# LIS3MDL.net
KiCad netlist of a schematic drawn in EAGLE
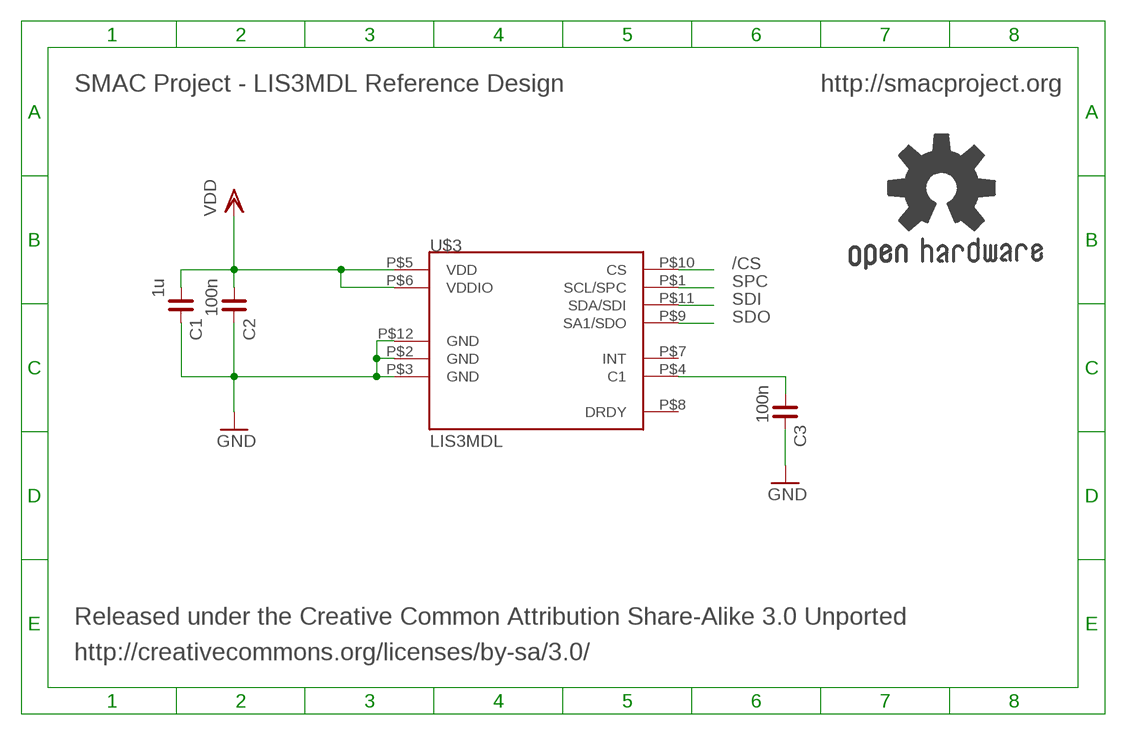
[diagram p0: schematic, sheet 1]

(export (version "E")
  (design (tool "Eeschema 10.0.6"))
  (components
    (comp (ref "C1")
      (value "1u")
      (footprint "eagle-import:C0402")
      (libsource (lib "eagle-import") (part "C_0402"))
    )
    (comp (ref "C2")
      (value "100n")
      (footprint "eagle-import:C0402")
      (libsource (lib "eagle-import") (part "C_0402"))
    )
    (comp (ref "C3")
      (value "100n")
      (footprint "eagle-import:C0402")
      (libsource (lib "eagle-import") (part "C_0402"))
    )
    (comp (ref "GOLD_ORB_SM1")
      (value "OSHWLOGO_REF_SM")
      (footprint "eagle-import:OSHW2REF")
      (libsource (lib "eagle-import") (part "OSHWLOGO_REF_SM"))
    )
    (comp (ref "U$3")
      (value "LIS3MDL")
      (footprint "eagle-import:VFLGA-2X2X1")
      (libsource (lib "eagle-import") (part "LIS3MDL"))
    )
  )
  (nets
    (net (code "1") (name "/SDI") (class "Default")
      (node (ref "U$3") (pin "P$11") (pinfunction "SDA/SDI_P$11") (pintype "bidirectional"))
    )
    (net (code "2") (name "/SDO") (class "Default")
      (node (ref "U$3") (pin "P$9") (pinfunction "SA1/SDO_P$9") (pintype "bidirectional"))
    )
    (net (code "3") (name "/SPC") (class "Default")
      (node (ref "U$3") (pin "P$1") (pinfunction "SCL/SPC_P$1") (pintype "bidirectional"))
    )
    (net (code "4") (name "/{slash}CS") (class "Default")
      (node (ref "U$3") (pin "P$10") (pinfunction "CS_P$10") (pintype "bidirectional"))
    )
    (net (code "5") (name "GND") (class "Default")
      (node (ref "C1") (pin "2") (pinfunction "2_2") (pintype "passive"))
      (node (ref "C2") (pin "2") (pinfunction "2_2") (pintype "passive"))
      (node (ref "C3") (pin "2") (pinfunction "2_2") (pintype "passive"))
      (node (ref "U$3") (pin "P$12") (pinfunction "GND_P$12") (pintype "bidirectional"))
      (node (ref "U$3") (pin "P$2") (pinfunction "GND_P$2") (pintype "bidirectional"))
      (node (ref "U$3") (pin "P$3") (pinfunction "GND_P$3") (pintype "bidirectional"))
    )
    (net (code "6") (name "Net-(U$3-C1)") (class "Default")
      (node (ref "C3") (pin "1") (pinfunction "1_1") (pintype "passive"))
      (node (ref "U$3") (pin "P$4") (pinfunction "C1_P$4") (pintype "bidirectional"))
    )
    (net (code "7") (name "VDD") (class "Default")
      (node (ref "C1") (pin "1") (pinfunction "1_1") (pintype "passive"))
      (node (ref "C2") (pin "1") (pinfunction "1_1") (pintype "passive"))
      (node (ref "U$3") (pin "P$5") (pinfunction "VDD_P$5") (pintype "bidirectional"))
      (node (ref "U$3") (pin "P$6") (pinfunction "VDDIO_P$6") (pintype "bidirectional"))
    )
    (net (code "8") (name "unconnected-(U$3-DRDY-PadP$8)") (class "Default")
      (node (ref "U$3") (pin "P$8") (pinfunction "DRDY_P$8") (pintype "bidirectional"))
    )
    (net (code "9") (name "unconnected-(U$3-INT-PadP$7)") (class "Default")
      (node (ref "U$3") (pin "P$7") (pinfunction "INT_P$7") (pintype "bidirectional"))
    )
  )
)
